# io_board.net
KiCad netlist of a schematic drawn in EAGLE
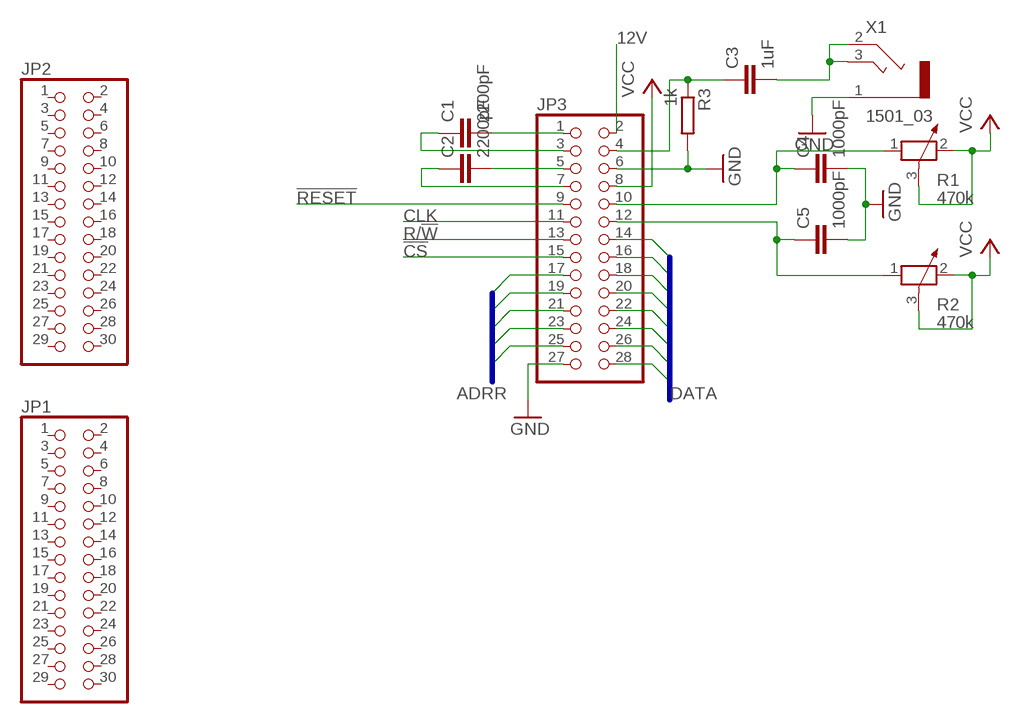
[diagram p0: schematic, sheet 1]

(export (version "E")
  (design (tool "Eeschema 10.0.6"))
  (components
    (comp (ref "C1")
      (value "2200pF")
      (footprint "eagle-import:C1206")
      (libsource (lib "eagle-import") (part "C-EUC1206"))
    )
    (comp (ref "C2")
      (value "2200pF")
      (footprint "eagle-import:C1206")
      (libsource (lib "eagle-import") (part "C-EUC1206"))
    )
    (comp (ref "C3")
      (value "1uF")
      (footprint "eagle-import:C1206")
      (libsource (lib "eagle-import") (part "C-EUC1206"))
    )
    (comp (ref "C4")
      (value "1000pF")
      (footprint "eagle-import:C1206")
      (libsource (lib "eagle-import") (part "C-EUC1206"))
    )
    (comp (ref "C5")
      (value "1000pF")
      (footprint "eagle-import:C1206")
      (libsource (lib "eagle-import") (part "C-EUC1206"))
    )
    (comp (ref "JP1")
      (value "PINHD-2X15")
      (footprint "eagle-import:2X15")
      (libsource (lib "eagle-import") (part "PINHD-2X15"))
    )
    (comp (ref "JP2")
      (value "PINHD-2X15")
      (footprint "eagle-import:2X15")
      (libsource (lib "eagle-import") (part "PINHD-2X15"))
    )
    (comp (ref "JP3")
      (value "PINHD-2X14")
      (footprint "eagle-import:2X14")
      (libsource (lib "eagle-import") (part "PINHD-2X14"))
    )
    (comp (ref "R1")
      (value "470k")
      (footprint "eagle-import:PT-10")
      (libsource (lib "eagle-import") (part "POTENTIOMETER_PT-10"))
    )
    (comp (ref "R2")
      (value "470k")
      (footprint "eagle-import:PT-10")
      (libsource (lib "eagle-import") (part "POTENTIOMETER_PT-10"))
    )
    (comp (ref "R3")
      (value "1k")
      (footprint "eagle-import:R0805")
      (libsource (lib "eagle-import") (part "R-EU_R0805"))
    )
    (comp (ref "X1")
      (value "1501_03")
      (footprint "eagle-import:1501_03")
      (libsource (lib "eagle-import") (part "1501_03"))
    )
  )
  (nets
    (net (code "3") (name "/12V") (class "Default")
      (node (ref "JP3") (pin "2") (pinfunction "2_2") (pintype "passive"))
    )
    (net (code "4") (name "/CLK") (class "Default")
      (node (ref "JP3") (pin "11") (pinfunction "11_11") (pintype "passive"))
    )
    (net (code "5") (name "/R{slash}~{W}") (class "Default")
      (node (ref "JP3") (pin "13") (pinfunction "13_13") (pintype "passive"))
    )
    (net (code "8") (name "/~{CS}") (class "Default")
      (node (ref "JP3") (pin "15") (pinfunction "15_15") (pintype "passive"))
    )
    (net (code "9") (name "/~{RESET}") (class "Default")
      (node (ref "JP3") (pin "9") (pinfunction "9_9") (pintype "passive"))
    )
    (net (code "10") (name "GND") (class "Default")
      (node (ref "C4") (pin "2") (pinfunction "2_2") (pintype "passive"))
      (node (ref "C5") (pin "2") (pinfunction "2_2") (pintype "passive"))
      (node (ref "JP3") (pin "27") (pinfunction "27_27") (pintype "passive"))
      (node (ref "JP3") (pin "6") (pinfunction "6_6") (pintype "passive"))
      (node (ref "R3") (pin "2") (pinfunction "2_2") (pintype "passive"))
      (node (ref "X1") (pin "1") (pinfunction "1_1") (pintype "passive"))
    )
    (net (code "11") (name "Net-(C1-Pad1)") (class "Default")
      (node (ref "C1") (pin "1") (pinfunction "1_1") (pintype "passive"))
      (node (ref "JP3") (pin "3") (pinfunction "3_3") (pintype "passive"))
    )
    (net (code "12") (name "Net-(C1-Pad2)") (class "Default")
      (node (ref "C1") (pin "2") (pinfunction "2_2") (pintype "passive"))
      (node (ref "JP3") (pin "1") (pinfunction "1_1") (pintype "passive"))
    )
    (net (code "13") (name "Net-(C2-Pad1)") (class "Default")
      (node (ref "C2") (pin "1") (pinfunction "1_1") (pintype "passive"))
      (node (ref "JP3") (pin "7") (pinfunction "7_7") (pintype "passive"))
    )
    (net (code "14") (name "Net-(C2-Pad2)") (class "Default")
      (node (ref "C2") (pin "2") (pinfunction "2_2") (pintype "passive"))
      (node (ref "JP3") (pin "5") (pinfunction "5_5") (pintype "passive"))
    )
    (net (code "15") (name "Net-(C3-Pad1)") (class "Default")
      (node (ref "C3") (pin "1") (pinfunction "1_1") (pintype "passive"))
      (node (ref "JP3") (pin "4") (pinfunction "4_4") (pintype "passive"))
      (node (ref "R3") (pin "1") (pinfunction "1_1") (pintype "passive"))
    )
    (net (code "16") (name "Net-(C3-Pad2)") (class "Default")
      (node (ref "C3") (pin "2") (pinfunction "2_2") (pintype "passive"))
      (node (ref "X1") (pin "2") (pinfunction "2_2") (pintype "passive"))
      (node (ref "X1") (pin "3") (pinfunction "3_3") (pintype "passive"))
    )
    (net (code "17") (name "Net-(C4-Pad1)") (class "Default")
      (node (ref "C4") (pin "1") (pinfunction "1_1") (pintype "passive"))
      (node (ref "JP3") (pin "10") (pinfunction "10_10") (pintype "passive"))
      (node (ref "R1") (pin "1") (pinfunction "1_1") (pintype "passive"))
    )
    (net (code "18") (name "Net-(C5-Pad1)") (class "Default")
      (node (ref "C5") (pin "1") (pinfunction "1_1") (pintype "passive"))
      (node (ref "JP3") (pin "12") (pinfunction "12_12") (pintype "passive"))
      (node (ref "R2") (pin "1") (pinfunction "1_1") (pintype "passive"))
    )
    (net (code "19") (name "VCC") (class "Default")
      (node (ref "JP3") (pin "8") (pinfunction "8_8") (pintype "passive"))
      (node (ref "R1") (pin "2") (pinfunction "2_2") (pintype "passive"))
      (node (ref "R1") (pin "3") (pinfunction "3_3") (pintype "passive"))
      (node (ref "R2") (pin "2") (pinfunction "2_2") (pintype "passive"))
      (node (ref "R2") (pin "3") (pinfunction "3_3") (pintype "passive"))
    )
    (net (code "20") (name "unconnected-(JP1-Pad1)") (class "Default")
      (node (ref "JP1") (pin "1") (pinfunction "1_1") (pintype "passive"))
    )
    (net (code "21") (name "unconnected-(JP1-Pad2)") (class "Default")
      (node (ref "JP1") (pin "2") (pinfunction "2_2") (pintype "passive"))
    )
    (net (code "22") (name "unconnected-(JP1-Pad3)") (class "Default")
      (node (ref "JP1") (pin "3") (pinfunction "3_3") (pintype "passive"))
    )
    (net (code "23") (name "unconnected-(JP1-Pad4)") (class "Default")
      (node (ref "JP1") (pin "4") (pinfunction "4_4") (pintype "passive"))
    )
    (net (code "24") (name "unconnected-(JP1-Pad5)") (class "Default")
      (node (ref "JP1") (pin "5") (pinfunction "5_5") (pintype "passive"))
    )
    (net (code "25") (name "unconnected-(JP1-Pad6)") (class "Default")
      (node (ref "JP1") (pin "6") (pinfunction "6_6") (pintype "passive"))
    )
    (net (code "26") (name "unconnected-(JP1-Pad7)") (class "Default")
      (node (ref "JP1") (pin "7") (pinfunction "7_7") (pintype "passive"))
    )
    (net (code "27") (name "unconnected-(JP1-Pad8)") (class "Default")
      (node (ref "JP1") (pin "8") (pinfunction "8_8") (pintype "passive"))
    )
    (net (code "28") (name "unconnected-(JP1-Pad9)") (class "Default")
      (node (ref "JP1") (pin "9") (pinfunction "9_9") (pintype "passive"))
    )
    (net (code "29") (name "unconnected-(JP1-Pad10)") (class "Default")
      (node (ref "JP1") (pin "10") (pinfunction "10_10") (pintype "passive"))
    )
    (net (code "30") (name "unconnected-(JP1-Pad11)") (class "Default")
      (node (ref "JP1") (pin "11") (pinfunction "11_11") (pintype "passive"))
    )
    (net (code "31") (name "unconnected-(JP1-Pad12)") (class "Default")
      (node (ref "JP1") (pin "12") (pinfunction "12_12") (pintype "passive"))
    )
    (net (code "32") (name "unconnected-(JP1-Pad13)") (class "Default")
      (node (ref "JP1") (pin "13") (pinfunction "13_13") (pintype "passive"))
    )
    (net (code "33") (name "unconnected-(JP1-Pad14)") (class "Default")
      (node (ref "JP1") (pin "14") (pinfunction "14_14") (pintype "passive"))
    )
    (net (code "34") (name "unconnected-(JP1-Pad15)") (class "Default")
      (node (ref "JP1") (pin "15") (pinfunction "15_15") (pintype "passive"))
    )
    (net (code "35") (name "unconnected-(JP1-Pad16)") (class "Default")
      (node (ref "JP1") (pin "16") (pinfunction "16_16") (pintype "passive"))
    )
    (net (code "36") (name "unconnected-(JP1-Pad17)") (class "Default")
      (node (ref "JP1") (pin "17") (pinfunction "17_17") (pintype "passive"))
    )
    (net (code "37") (name "unconnected-(JP1-Pad18)") (class "Default")
      (node (ref "JP1") (pin "18") (pinfunction "18_18") (pintype "passive"))
    )
    (net (code "38") (name "unconnected-(JP1-Pad19)") (class "Default")
      (node (ref "JP1") (pin "19") (pinfunction "19_19") (pintype "passive"))
    )
    (net (code "39") (name "unconnected-(JP1-Pad20)") (class "Default")
      (node (ref "JP1") (pin "20") (pinfunction "20_20") (pintype "passive"))
    )
    (net (code "40") (name "unconnected-(JP1-Pad21)") (class "Default")
      (node (ref "JP1") (pin "21") (pinfunction "21_21") (pintype "passive"))
    )
    (net (code "41") (name "unconnected-(JP1-Pad22)") (class "Default")
      (node (ref "JP1") (pin "22") (pinfunction "22_22") (pintype "passive"))
    )
    (net (code "42") (name "unconnected-(JP1-Pad23)") (class "Default")
      (node (ref "JP1") (pin "23") (pinfunction "23_23") (pintype "passive"))
    )
    (net (code "43") (name "unconnected-(JP1-Pad24)") (class "Default")
      (node (ref "JP1") (pin "24") (pinfunction "24_24") (pintype "passive"))
    )
    (net (code "44") (name "unconnected-(JP1-Pad25)") (class "Default")
      (node (ref "JP1") (pin "25") (pinfunction "25_25") (pintype "passive"))
    )
    (net (code "45") (name "unconnected-(JP1-Pad26)") (class "Default")
      (node (ref "JP1") (pin "26") (pinfunction "26_26") (pintype "passive"))
    )
    (net (code "46") (name "unconnected-(JP1-Pad27)") (class "Default")
      (node (ref "JP1") (pin "27") (pinfunction "27_27") (pintype "passive"))
    )
    (net (code "47") (name "unconnected-(JP1-Pad28)") (class "Default")
      (node (ref "JP1") (pin "28") (pinfunction "28_28") (pintype "passive"))
    )
    (net (code "48") (name "unconnected-(JP1-Pad29)") (class "Default")
      (node (ref "JP1") (pin "29") (pinfunction "29_29") (pintype "passive"))
    )
    (net (code "49") (name "unconnected-(JP1-Pad30)") (class "Default")
      (node (ref "JP1") (pin "30") (pinfunction "30_30") (pintype "passive"))
    )
    (net (code "50") (name "unconnected-(JP2-Pad1)") (class "Default")
      (node (ref "JP2") (pin "1") (pinfunction "1_1") (pintype "passive"))
    )
    (net (code "51") (name "unconnected-(JP2-Pad2)") (class "Default")
      (node (ref "JP2") (pin "2") (pinfunction "2_2") (pintype "passive"))
    )
    (net (code "52") (name "unconnected-(JP2-Pad3)") (class "Default")
      (node (ref "JP2") (pin "3") (pinfunction "3_3") (pintype "passive"))
    )
    (net (code "53") (name "unconnected-(JP2-Pad4)") (class "Default")
      (node (ref "JP2") (pin "4") (pinfunction "4_4") (pintype "passive"))
    )
    (net (code "54") (name "unconnected-(JP2-Pad5)") (class "Default")
      (node (ref "JP2") (pin "5") (pinfunction "5_5") (pintype "passive"))
    )
    (net (code "55") (name "unconnected-(JP2-Pad6)") (class "Default")
      (node (ref "JP2") (pin "6") (pinfunction "6_6") (pintype "passive"))
    )
    (net (code "56") (name "unconnected-(JP2-Pad7)") (class "Default")
      (node (ref "JP2") (pin "7") (pinfunction "7_7") (pintype "passive"))
    )
    (net (code "57") (name "unconnected-(JP2-Pad8)") (class "Default")
      (node (ref "JP2") (pin "8") (pinfunction "8_8") (pintype "passive"))
    )
    (net (code "58") (name "unconnected-(JP2-Pad9)") (class "Default")
      (node (ref "JP2") (pin "9") (pinfunction "9_9") (pintype "passive"))
    )
    (net (code "59") (name "unconnected-(JP2-Pad10)") (class "Default")
      (node (ref "JP2") (pin "10") (pinfunction "10_10") (pintype "passive"))
    )
    (net (code "60") (name "unconnected-(JP2-Pad11)") (class "Default")
      (node (ref "JP2") (pin "11") (pinfunction "11_11") (pintype "passive"))
    )
    (net (code "61") (name "unconnected-(JP2-Pad12)") (class "Default")
      (node (ref "JP2") (pin "12") (pinfunction "12_12") (pintype "passive"))
    )
    (net (code "62") (name "unconnected-(JP2-Pad13)") (class "Default")
      (node (ref "JP2") (pin "13") (pinfunction "13_13") (pintype "passive"))
    )
    (net (code "63") (name "unconnected-(JP2-Pad14)") (class "Default")
      (node (ref "JP2") (pin "14") (pinfunction "14_14") (pintype "passive"))
    )
    (net (code "64") (name "unconnected-(JP2-Pad15)") (class "Default")
      (node (ref "JP2") (pin "15") (pinfunction "15_15") (pintype "passive"))
    )
    (net (code "65") (name "unconnected-(JP2-Pad16)") (class "Default")
      (node (ref "JP2") (pin "16") (pinfunction "16_16") (pintype "passive"))
    )
    (net (code "66") (name "unconnected-(JP2-Pad17)") (class "Default")
      (node (ref "JP2") (pin "17") (pinfunction "17_17") (pintype "passive"))
    )
    (net (code "67") (name "unconnected-(JP2-Pad18)") (class "Default")
      (node (ref "JP2") (pin "18") (pinfunction "18_18") (pintype "passive"))
    )
    (net (code "68") (name "unconnected-(JP2-Pad19)") (class "Default")
      (node (ref "JP2") (pin "19") (pinfunction "19_19") (pintype "passive"))
    )
    (net (code "69") (name "unconnected-(JP2-Pad20)") (class "Default")
      (node (ref "JP2") (pin "20") (pinfunction "20_20") (pintype "passive"))
    )
    (net (code "70") (name "unconnected-(JP2-Pad21)") (class "Default")
      (node (ref "JP2") (pin "21") (pinfunction "21_21") (pintype "passive"))
    )
    (net (code "71") (name "unconnected-(JP2-Pad22)") (class "Default")
      (node (ref "JP2") (pin "22") (pinfunction "22_22") (pintype "passive"))
    )
    (net (code "72") (name "unconnected-(JP2-Pad23)") (class "Default")
      (node (ref "JP2") (pin "23") (pinfunction "23_23") (pintype "passive"))
    )
    (net (code "73") (name "unconnected-(JP2-Pad24)") (class "Default")
      (node (ref "JP2") (pin "24") (pinfunction "24_24") (pintype "passive"))
    )
    (net (code "74") (name "unconnected-(JP2-Pad25)") (class "Default")
      (node (ref "JP2") (pin "25") (pinfunction "25_25") (pintype "passive"))
    )
    (net (code "75") (name "unconnected-(JP2-Pad26)") (class "Default")
      (node (ref "JP2") (pin "26") (pinfunction "26_26") (pintype "passive"))
    )
    (net (code "76") (name "unconnected-(JP2-Pad27)") (class "Default")
      (node (ref "JP2") (pin "27") (pinfunction "27_27") (pintype "passive"))
    )
    (net (code "77") (name "unconnected-(JP2-Pad28)") (class "Default")
      (node (ref "JP2") (pin "28") (pinfunction "28_28") (pintype "passive"))
    )
    (net (code "78") (name "unconnected-(JP2-Pad29)") (class "Default")
      (node (ref "JP2") (pin "29") (pinfunction "29_29") (pintype "passive"))
    )
    (net (code "79") (name "unconnected-(JP2-Pad30)") (class "Default")
      (node (ref "JP2") (pin "30") (pinfunction "30_30") (pintype "passive"))
    )
    (net (code "80") (name "unconnected-(JP3-Pad14)") (class "Default")
      (node (ref "JP3") (pin "14") (pinfunction "14_14") (pintype "passive"))
    )
    (net (code "81") (name "unconnected-(JP3-Pad16)") (class "Default")
      (node (ref "JP3") (pin "16") (pinfunction "16_16") (pintype "passive"))
    )
    (net (code "82") (name "unconnected-(JP3-Pad17)") (class "Default")
      (node (ref "JP3") (pin "17") (pinfunction "17_17") (pintype "passive"))
    )
    (net (code "83") (name "unconnected-(JP3-Pad18)") (class "Default")
      (node (ref "JP3") (pin "18") (pinfunction "18_18") (pintype "passive"))
    )
    (net (code "84") (name "unconnected-(JP3-Pad19)") (class "Default")
      (node (ref "JP3") (pin "19") (pinfunction "19_19") (pintype "passive"))
    )
    (net (code "85") (name "unconnected-(JP3-Pad20)") (class "Default")
      (node (ref "JP3") (pin "20") (pinfunction "20_20") (pintype "passive"))
    )
    (net (code "86") (name "unconnected-(JP3-Pad21)") (class "Default")
      (node (ref "JP3") (pin "21") (pinfunction "21_21") (pintype "passive"))
    )
    (net (code "87") (name "unconnected-(JP3-Pad22)") (class "Default")
      (node (ref "JP3") (pin "22") (pinfunction "22_22") (pintype "passive"))
    )
    (net (code "88") (name "unconnected-(JP3-Pad23)") (class "Default")
      (node (ref "JP3") (pin "23") (pinfunction "23_23") (pintype "passive"))
    )
    (net (code "89") (name "unconnected-(JP3-Pad24)") (class "Default")
      (node (ref "JP3") (pin "24") (pinfunction "24_24") (pintype "passive"))
    )
    (net (code "90") (name "unconnected-(JP3-Pad25)") (class "Default")
      (node (ref "JP3") (pin "25") (pinfunction "25_25") (pintype "passive"))
    )
    (net (code "91") (name "unconnected-(JP3-Pad26)") (class "Default")
      (node (ref "JP3") (pin "26") (pinfunction "26_26") (pintype "passive"))
    )
    (net (code "92") (name "unconnected-(JP3-Pad28)") (class "Default")
      (node (ref "JP3") (pin "28") (pinfunction "28_28") (pintype "passive"))
    )
  )
)
